# 5_wled.net
KiCad netlist of a schematic drawn in Altium Designer
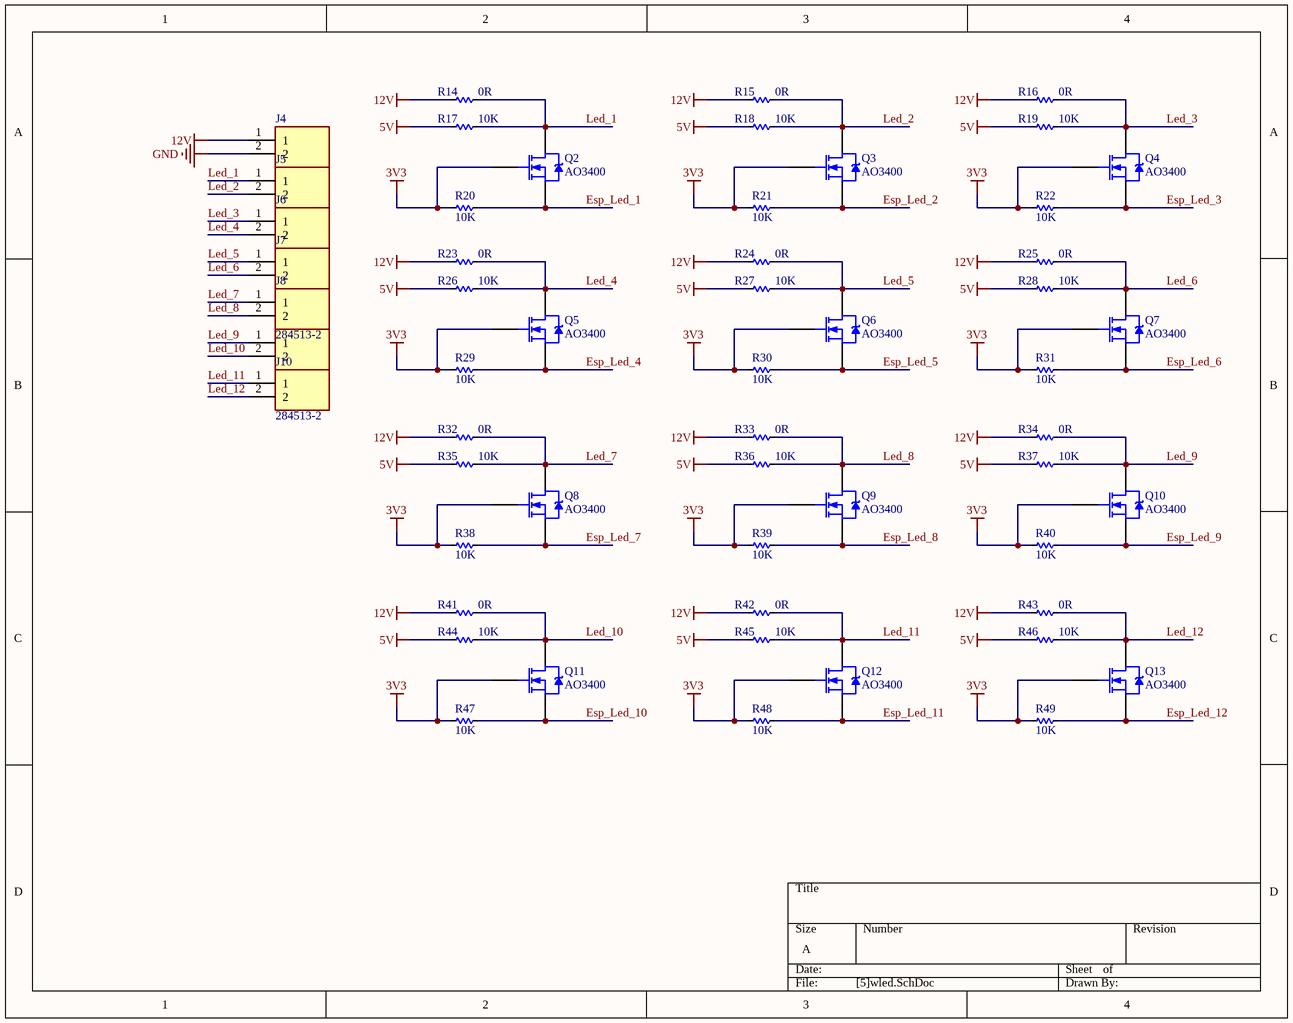
[diagram p0: [5]wled.SchDoc]

(export (version "E")
  (design (tool "Eeschema 10.0.6"))
  (components
    (comp (ref "J4")
      (value "284513-2")
      (footprint "SamacSys:SHDRRA2W80P0X381_1X2_863X920X730P")
      (description "Connector")
      (fields (field (name "MOUSER PART NUMBER") "571-284513-2"))
      (libsource (lib "SamacSys") (part "284513-2"))
    )
    (comp (ref "J5")
      (value "284513-2")
      (footprint "SamacSys:SHDRRA2W80P0X381_1X2_863X920X730P")
      (description "Connector")
      (fields (field (name "MOUSER PART NUMBER") "571-284513-2"))
      (libsource (lib "SamacSys") (part "284513-2"))
    )
    (comp (ref "J6")
      (value "284513-2")
      (footprint "SamacSys:SHDRRA2W80P0X381_1X2_863X920X730P")
      (description "Connector")
      (fields (field (name "MOUSER PART NUMBER") "571-284513-2"))
      (libsource (lib "SamacSys") (part "284513-2"))
    )
    (comp (ref "J7")
      (value "284513-2")
      (footprint "SamacSys:SHDRRA2W80P0X381_1X2_863X920X730P")
      (description "Connector")
      (fields (field (name "MOUSER PART NUMBER") "571-284513-2"))
      (libsource (lib "SamacSys") (part "284513-2"))
    )
    (comp (ref "J8")
      (value "284513-2")
      (footprint "SamacSys:SHDRRA2W80P0X381_1X2_863X920X730P")
      (description "Connector")
      (fields (field (name "MOUSER PART NUMBER") "571-284513-2"))
      (libsource (lib "SamacSys") (part "284513-2"))
    )
    (comp (ref "J9")
      (value "284513-2")
      (footprint "SamacSys:SHDRRA2W80P0X381_1X2_863X920X730P")
      (description "Connector")
      (fields (field (name "MOUSER PART NUMBER") "571-284513-2"))
      (libsource (lib "SamacSys") (part "284513-2"))
    )
    (comp (ref "J10")
      (value "284513-2")
      (footprint "SamacSys:SHDRRA2W80P0X381_1X2_863X920X730P")
      (description "Connector")
      (fields (field (name "MOUSER PART NUMBER") "571-284513-2"))
      (libsource (lib "SamacSys") (part "284513-2"))
    )
    (comp (ref "Q2")
      (value "AO3400")
      (footprint "SOT-23_N")
      (description "HEXFET Power MOSFET")
      (fields (field (name "PUBLISHER") "Altium Limited"))
      (libsource (lib "IR Discrete MOSFET - Power") (part "IRLML2402"))
    )
    (comp (ref "Q3")
      (value "AO3400")
      (footprint "SOT-23_N")
      (description "HEXFET Power MOSFET")
      (fields (field (name "PUBLISHER") "Altium Limited"))
      (libsource (lib "IR Discrete MOSFET - Power") (part "IRLML2402"))
    )
    (comp (ref "Q4")
      (value "AO3400")
      (footprint "SOT-23_N")
      (description "HEXFET Power MOSFET")
      (fields (field (name "PUBLISHER") "Altium Limited"))
      (libsource (lib "IR Discrete MOSFET - Power") (part "IRLML2402"))
    )
    (comp (ref "Q5")
      (value "AO3400")
      (footprint "SOT-23_N")
      (description "HEXFET Power MOSFET")
      (fields (field (name "PUBLISHER") "Altium Limited"))
      (libsource (lib "IR Discrete MOSFET - Power") (part "IRLML2402"))
    )
    (comp (ref "Q6")
      (value "AO3400")
      (footprint "SOT-23_N")
      (description "HEXFET Power MOSFET")
      (fields (field (name "PUBLISHER") "Altium Limited"))
      (libsource (lib "IR Discrete MOSFET - Power") (part "IRLML2402"))
    )
    (comp (ref "Q7")
      (value "AO3400")
      (footprint "SOT-23_N")
      (description "HEXFET Power MOSFET")
      (fields (field (name "PUBLISHER") "Altium Limited"))
      (libsource (lib "IR Discrete MOSFET - Power") (part "IRLML2402"))
    )
    (comp (ref "Q8")
      (value "AO3400")
      (footprint "SOT-23_N")
      (description "HEXFET Power MOSFET")
      (fields (field (name "PUBLISHER") "Altium Limited"))
      (libsource (lib "IR Discrete MOSFET - Power") (part "IRLML2402"))
    )
    (comp (ref "Q9")
      (value "AO3400")
      (footprint "SOT-23_N")
      (description "HEXFET Power MOSFET")
      (fields (field (name "PUBLISHER") "Altium Limited"))
      (libsource (lib "IR Discrete MOSFET - Power") (part "IRLML2402"))
    )
    (comp (ref "Q10")
      (value "AO3400")
      (footprint "SOT-23_N")
      (description "HEXFET Power MOSFET")
      (fields (field (name "PUBLISHER") "Altium Limited"))
      (libsource (lib "IR Discrete MOSFET - Power") (part "IRLML2402"))
    )
    (comp (ref "Q11")
      (value "AO3400")
      (footprint "SOT-23_N")
      (description "HEXFET Power MOSFET")
      (fields (field (name "PUBLISHER") "Altium Limited"))
      (libsource (lib "IR Discrete MOSFET - Power") (part "IRLML2402"))
    )
    (comp (ref "Q12")
      (value "AO3400")
      (footprint "SOT-23_N")
      (description "HEXFET Power MOSFET")
      (fields (field (name "PUBLISHER") "Altium Limited"))
      (libsource (lib "IR Discrete MOSFET - Power") (part "IRLML2402"))
    )
    (comp (ref "Q13")
      (value "AO3400")
      (footprint "SOT-23_N")
      (description "HEXFET Power MOSFET")
      (fields (field (name "PUBLISHER") "Altium Limited"))
      (libsource (lib "IR Discrete MOSFET - Power") (part "IRLML2402"))
    )
    (comp (ref "R14")
      (value "0R")
      (footprint "RES-SMD-0805")
      (description "Resistor")
      (fields
        (field (name "MANUFACTURER") "Generic Components")
        (field (name "PUBLISHER") "Altium Hobart Technology Centre")
      )
      (libsource (lib "LIBRARY") (part "Res-SMD"))
    )
    (comp (ref "R15")
      (value "0R")
      (footprint "RES-SMD-0805")
      (description "Resistor")
      (fields
        (field (name "MANUFACTURER") "Generic Components")
        (field (name "PUBLISHER") "Altium Hobart Technology Centre")
      )
      (libsource (lib "LIBRARY") (part "Res-SMD"))
    )
    (comp (ref "R16")
      (value "0R")
      (footprint "RES-SMD-0805")
      (description "Resistor")
      (fields
        (field (name "MANUFACTURER") "Generic Components")
        (field (name "PUBLISHER") "Altium Hobart Technology Centre")
      )
      (libsource (lib "LIBRARY") (part "Res-SMD"))
    )
    (comp (ref "R17")
      (value "10K")
      (footprint "RES-SMD-0805")
      (description "Resistor")
      (fields
        (field (name "MANUFACTURER") "Generic Components")
        (field (name "PUBLISHER") "Altium Hobart Technology Centre")
      )
      (libsource (lib "LIBRARY") (part "Res-SMD"))
    )
    (comp (ref "R18")
      (value "10K")
      (footprint "RES-SMD-0805")
      (description "Resistor")
      (fields
        (field (name "MANUFACTURER") "Generic Components")
        (field (name "PUBLISHER") "Altium Hobart Technology Centre")
      )
      (libsource (lib "LIBRARY") (part "Res-SMD"))
    )
    (comp (ref "R19")
      (value "10K")
      (footprint "RES-SMD-0805")
      (description "Resistor")
      (fields
        (field (name "MANUFACTURER") "Generic Components")
        (field (name "PUBLISHER") "Altium Hobart Technology Centre")
      )
      (libsource (lib "LIBRARY") (part "Res-SMD"))
    )
    (comp (ref "R20")
      (value "10K")
      (footprint "RES-SMD-0805")
      (description "Resistor")
      (fields
        (field (name "MANUFACTURER") "Generic Components")
        (field (name "PUBLISHER") "Altium Hobart Technology Centre")
      )
      (libsource (lib "LIBRARY") (part "Res-SMD"))
    )
    (comp (ref "R21")
      (value "10K")
      (footprint "RES-SMD-0805")
      (description "Resistor")
      (fields
        (field (name "MANUFACTURER") "Generic Components")
        (field (name "PUBLISHER") "Altium Hobart Technology Centre")
      )
      (libsource (lib "LIBRARY") (part "Res-SMD"))
    )
    (comp (ref "R22")
      (value "10K")
      (footprint "RES-SMD-0805")
      (description "Resistor")
      (fields
        (field (name "MANUFACTURER") "Generic Components")
        (field (name "PUBLISHER") "Altium Hobart Technology Centre")
      )
      (libsource (lib "LIBRARY") (part "Res-SMD"))
    )
    (comp (ref "R23")
      (value "0R")
      (footprint "RES-SMD-0805")
      (description "Resistor")
      (fields
        (field (name "MANUFACTURER") "Generic Components")
        (field (name "PUBLISHER") "Altium Hobart Technology Centre")
      )
      (libsource (lib "LIBRARY") (part "Res-SMD"))
    )
    (comp (ref "R24")
      (value "0R")
      (footprint "RES-SMD-0805")
      (description "Resistor")
      (fields
        (field (name "MANUFACTURER") "Generic Components")
        (field (name "PUBLISHER") "Altium Hobart Technology Centre")
      )
      (libsource (lib "LIBRARY") (part "Res-SMD"))
    )
    (comp (ref "R25")
      (value "0R")
      (footprint "RES-SMD-0805")
      (description "Resistor")
      (fields
        (field (name "MANUFACTURER") "Generic Components")
        (field (name "PUBLISHER") "Altium Hobart Technology Centre")
      )
      (libsource (lib "LIBRARY") (part "Res-SMD"))
    )
    (comp (ref "R26")
      (value "10K")
      (footprint "RES-SMD-0805")
      (description "Resistor")
      (fields
        (field (name "MANUFACTURER") "Generic Components")
        (field (name "PUBLISHER") "Altium Hobart Technology Centre")
      )
      (libsource (lib "LIBRARY") (part "Res-SMD"))
    )
    (comp (ref "R27")
      (value "10K")
      (footprint "RES-SMD-0805")
      (description "Resistor")
      (fields
        (field (name "MANUFACTURER") "Generic Components")
        (field (name "PUBLISHER") "Altium Hobart Technology Centre")
      )
      (libsource (lib "LIBRARY") (part "Res-SMD"))
    )
    (comp (ref "R28")
      (value "10K")
      (footprint "RES-SMD-0805")
      (description "Resistor")
      (fields
        (field (name "MANUFACTURER") "Generic Components")
        (field (name "PUBLISHER") "Altium Hobart Technology Centre")
      )
      (libsource (lib "LIBRARY") (part "Res-SMD"))
    )
    (comp (ref "R29")
      (value "10K")
      (footprint "RES-SMD-0805")
      (description "Resistor")
      (fields
        (field (name "MANUFACTURER") "Generic Components")
        (field (name "PUBLISHER") "Altium Hobart Technology Centre")
      )
      (libsource (lib "LIBRARY") (part "Res-SMD"))
    )
    (comp (ref "R30")
      (value "10K")
      (footprint "RES-SMD-0805")
      (description "Resistor")
      (fields
        (field (name "MANUFACTURER") "Generic Components")
        (field (name "PUBLISHER") "Altium Hobart Technology Centre")
      )
      (libsource (lib "LIBRARY") (part "Res-SMD"))
    )
    (comp (ref "R31")
      (value "10K")
      (footprint "RES-SMD-0805")
      (description "Resistor")
      (fields
        (field (name "MANUFACTURER") "Generic Components")
        (field (name "PUBLISHER") "Altium Hobart Technology Centre")
      )
      (libsource (lib "LIBRARY") (part "Res-SMD"))
    )
    (comp (ref "R32")
      (value "0R")
      (footprint "RES-SMD-0805")
      (description "Resistor")
      (fields
        (field (name "MANUFACTURER") "Generic Components")
        (field (name "PUBLISHER") "Altium Hobart Technology Centre")
      )
      (libsource (lib "LIBRARY") (part "Res-SMD"))
    )
    (comp (ref "R33")
      (value "0R")
      (footprint "RES-SMD-0805")
      (description "Resistor")
      (fields
        (field (name "MANUFACTURER") "Generic Components")
        (field (name "PUBLISHER") "Altium Hobart Technology Centre")
      )
      (libsource (lib "LIBRARY") (part "Res-SMD"))
    )
    (comp (ref "R34")
      (value "0R")
      (footprint "RES-SMD-0805")
      (description "Resistor")
      (fields
        (field (name "MANUFACTURER") "Generic Components")
        (field (name "PUBLISHER") "Altium Hobart Technology Centre")
      )
      (libsource (lib "LIBRARY") (part "Res-SMD"))
    )
    (comp (ref "R35")
      (value "10K")
      (footprint "RES-SMD-0805")
      (description "Resistor")
      (fields
        (field (name "MANUFACTURER") "Generic Components")
        (field (name "PUBLISHER") "Altium Hobart Technology Centre")
      )
      (libsource (lib "LIBRARY") (part "Res-SMD"))
    )
    (comp (ref "R36")
      (value "10K")
      (footprint "RES-SMD-0805")
      (description "Resistor")
      (fields
        (field (name "MANUFACTURER") "Generic Components")
        (field (name "PUBLISHER") "Altium Hobart Technology Centre")
      )
      (libsource (lib "LIBRARY") (part "Res-SMD"))
    )
    (comp (ref "R37")
      (value "10K")
      (footprint "RES-SMD-0805")
      (description "Resistor")
      (fields
        (field (name "MANUFACTURER") "Generic Components")
        (field (name "PUBLISHER") "Altium Hobart Technology Centre")
      )
      (libsource (lib "LIBRARY") (part "Res-SMD"))
    )
    (comp (ref "R38")
      (value "10K")
      (footprint "RES-SMD-0805")
      (description "Resistor")
      (fields
        (field (name "MANUFACTURER") "Generic Components")
        (field (name "PUBLISHER") "Altium Hobart Technology Centre")
      )
      (libsource (lib "LIBRARY") (part "Res-SMD"))
    )
    (comp (ref "R39")
      (value "10K")
      (footprint "RES-SMD-0805")
      (description "Resistor")
      (fields
        (field (name "MANUFACTURER") "Generic Components")
        (field (name "PUBLISHER") "Altium Hobart Technology Centre")
      )
      (libsource (lib "LIBRARY") (part "Res-SMD"))
    )
    (comp (ref "R40")
      (value "10K")
      (footprint "RES-SMD-0805")
      (description "Resistor")
      (fields
        (field (name "MANUFACTURER") "Generic Components")
        (field (name "PUBLISHER") "Altium Hobart Technology Centre")
      )
      (libsource (lib "LIBRARY") (part "Res-SMD"))
    )
    (comp (ref "R41")
      (value "0R")
      (footprint "RES-SMD-0805")
      (description "Resistor")
      (fields
        (field (name "MANUFACTURER") "Generic Components")
        (field (name "PUBLISHER") "Altium Hobart Technology Centre")
      )
      (libsource (lib "LIBRARY") (part "Res-SMD"))
    )
    (comp (ref "R42")
      (value "0R")
      (footprint "RES-SMD-0805")
      (description "Resistor")
      (fields
        (field (name "MANUFACTURER") "Generic Components")
        (field (name "PUBLISHER") "Altium Hobart Technology Centre")
      )
      (libsource (lib "LIBRARY") (part "Res-SMD"))
    )
    (comp (ref "R43")
      (value "0R")
      (footprint "RES-SMD-0805")
      (description "Resistor")
      (fields
        (field (name "MANUFACTURER") "Generic Components")
        (field (name "PUBLISHER") "Altium Hobart Technology Centre")
      )
      (libsource (lib "LIBRARY") (part "Res-SMD"))
    )
    (comp (ref "R44")
      (value "10K")
      (footprint "RES-SMD-0805")
      (description "Resistor")
      (fields
        (field (name "MANUFACTURER") "Generic Components")
        (field (name "PUBLISHER") "Altium Hobart Technology Centre")
      )
      (libsource (lib "LIBRARY") (part "Res-SMD"))
    )
    (comp (ref "R45")
      (value "10K")
      (footprint "RES-SMD-0805")
      (description "Resistor")
      (fields
        (field (name "MANUFACTURER") "Generic Components")
        (field (name "PUBLISHER") "Altium Hobart Technology Centre")
      )
      (libsource (lib "LIBRARY") (part "Res-SMD"))
    )
    (comp (ref "R46")
      (value "10K")
      (footprint "RES-SMD-0805")
      (description "Resistor")
      (fields
        (field (name "MANUFACTURER") "Generic Components")
        (field (name "PUBLISHER") "Altium Hobart Technology Centre")
      )
      (libsource (lib "LIBRARY") (part "Res-SMD"))
    )
    (comp (ref "R47")
      (value "10K")
      (footprint "RES-SMD-0805")
      (description "Resistor")
      (fields
        (field (name "MANUFACTURER") "Generic Components")
        (field (name "PUBLISHER") "Altium Hobart Technology Centre")
      )
      (libsource (lib "LIBRARY") (part "Res-SMD"))
    )
    (comp (ref "R48")
      (value "10K")
      (footprint "RES-SMD-0805")
      (description "Resistor")
      (fields
        (field (name "MANUFACTURER") "Generic Components")
        (field (name "PUBLISHER") "Altium Hobart Technology Centre")
      )
      (libsource (lib "LIBRARY") (part "Res-SMD"))
    )
    (comp (ref "R49")
      (value "10K")
      (footprint "RES-SMD-0805")
      (description "Resistor")
      (fields
        (field (name "MANUFACTURER") "Generic Components")
        (field (name "PUBLISHER") "Altium Hobart Technology Centre")
      )
      (libsource (lib "LIBRARY") (part "Res-SMD"))
    )
  )
  (nets
    (net (code "1") (name "/Esp_Led_1") (class "Default")
      (node (ref "Q2") (pin "2") (pinfunction "S_2") (pintype "passive"))
      (node (ref "R20") (pin "2") (pinfunction "2_2") (pintype "passive"))
    )
    (net (code "2") (name "/Esp_Led_2") (class "Default")
      (node (ref "Q3") (pin "2") (pinfunction "S_2") (pintype "passive"))
      (node (ref "R21") (pin "2") (pinfunction "2_2") (pintype "passive"))
    )
    (net (code "3") (name "/Esp_Led_3") (class "Default")
      (node (ref "Q4") (pin "2") (pinfunction "S_2") (pintype "passive"))
      (node (ref "R22") (pin "2") (pinfunction "2_2") (pintype "passive"))
    )
    (net (code "4") (name "/Esp_Led_4") (class "Default")
      (node (ref "Q5") (pin "2") (pinfunction "S_2") (pintype "passive"))
      (node (ref "R29") (pin "2") (pinfunction "2_2") (pintype "passive"))
    )
    (net (code "5") (name "/Esp_Led_5") (class "Default")
      (node (ref "Q6") (pin "2") (pinfunction "S_2") (pintype "passive"))
      (node (ref "R30") (pin "2") (pinfunction "2_2") (pintype "passive"))
    )
    (net (code "6") (name "/Esp_Led_6") (class "Default")
      (node (ref "Q7") (pin "2") (pinfunction "S_2") (pintype "passive"))
      (node (ref "R31") (pin "2") (pinfunction "2_2") (pintype "passive"))
    )
    (net (code "7") (name "/Esp_Led_7") (class "Default")
      (node (ref "Q8") (pin "2") (pinfunction "S_2") (pintype "passive"))
      (node (ref "R38") (pin "2") (pinfunction "2_2") (pintype "passive"))
    )
    (net (code "8") (name "/Esp_Led_8") (class "Default")
      (node (ref "Q9") (pin "2") (pinfunction "S_2") (pintype "passive"))
      (node (ref "R39") (pin "2") (pinfunction "2_2") (pintype "passive"))
    )
    (net (code "9") (name "/Esp_Led_9") (class "Default")
      (node (ref "Q10") (pin "2") (pinfunction "S_2") (pintype "passive"))
      (node (ref "R40") (pin "2") (pinfunction "2_2") (pintype "passive"))
    )
    (net (code "10") (name "/Esp_Led_10") (class "Default")
      (node (ref "Q11") (pin "2") (pinfunction "S_2") (pintype "passive"))
      (node (ref "R47") (pin "2") (pinfunction "2_2") (pintype "passive"))
    )
    (net (code "11") (name "/Esp_Led_11") (class "Default")
      (node (ref "Q12") (pin "2") (pinfunction "S_2") (pintype "passive"))
      (node (ref "R48") (pin "2") (pinfunction "2_2") (pintype "passive"))
    )
    (net (code "12") (name "/Esp_Led_12") (class "Default")
      (node (ref "Q13") (pin "2") (pinfunction "S_2") (pintype "passive"))
      (node (ref "R49") (pin "2") (pinfunction "2_2") (pintype "passive"))
    )
    (net (code "13") (name "/Led_1") (class "Default")
      (node (ref "J5") (pin "1") (pinfunction "1_1") (pintype "passive"))
      (node (ref "Q2") (pin "3") (pinfunction "D_3") (pintype "passive"))
      (node (ref "R14") (pin "2") (pinfunction "2_2") (pintype "passive"))
      (node (ref "R17") (pin "2") (pinfunction "2_2") (pintype "passive"))
    )
    (net (code "14") (name "/Led_2") (class "Default")
      (node (ref "J5") (pin "2") (pinfunction "2_2") (pintype "passive"))
      (node (ref "Q3") (pin "3") (pinfunction "D_3") (pintype "passive"))
      (node (ref "R15") (pin "2") (pinfunction "2_2") (pintype "passive"))
      (node (ref "R18") (pin "2") (pinfunction "2_2") (pintype "passive"))
    )
    (net (code "15") (name "/Led_3") (class "Default")
      (node (ref "J6") (pin "1") (pinfunction "1_1") (pintype "passive"))
      (node (ref "Q4") (pin "3") (pinfunction "D_3") (pintype "passive"))
      (node (ref "R16") (pin "2") (pinfunction "2_2") (pintype "passive"))
      (node (ref "R19") (pin "2") (pinfunction "2_2") (pintype "passive"))
    )
    (net (code "16") (name "/Led_4") (class "Default")
      (node (ref "J6") (pin "2") (pinfunction "2_2") (pintype "passive"))
      (node (ref "Q5") (pin "3") (pinfunction "D_3") (pintype "passive"))
      (node (ref "R23") (pin "2") (pinfunction "2_2") (pintype "passive"))
      (node (ref "R26") (pin "2") (pinfunction "2_2") (pintype "passive"))
    )
    (net (code "17") (name "/Led_5") (class "Default")
      (node (ref "J7") (pin "1") (pinfunction "1_1") (pintype "passive"))
      (node (ref "Q6") (pin "3") (pinfunction "D_3") (pintype "passive"))
      (node (ref "R24") (pin "2") (pinfunction "2_2") (pintype "passive"))
      (node (ref "R27") (pin "2") (pinfunction "2_2") (pintype "passive"))
    )
    (net (code "18") (name "/Led_6") (class "Default")
      (node (ref "J7") (pin "2") (pinfunction "2_2") (pintype "passive"))
      (node (ref "Q7") (pin "3") (pinfunction "D_3") (pintype "passive"))
      (node (ref "R25") (pin "2") (pinfunction "2_2") (pintype "passive"))
      (node (ref "R28") (pin "2") (pinfunction "2_2") (pintype "passive"))
    )
    (net (code "19") (name "/Led_7") (class "Default")
      (node (ref "J8") (pin "1") (pinfunction "1_1") (pintype "passive"))
      (node (ref "Q8") (pin "3") (pinfunction "D_3") (pintype "passive"))
      (node (ref "R32") (pin "2") (pinfunction "2_2") (pintype "passive"))
      (node (ref "R35") (pin "2") (pinfunction "2_2") (pintype "passive"))
    )
    (net (code "20") (name "/Led_8") (class "Default")
      (node (ref "J8") (pin "2") (pinfunction "2_2") (pintype "passive"))
      (node (ref "Q9") (pin "3") (pinfunction "D_3") (pintype "passive"))
      (node (ref "R33") (pin "2") (pinfunction "2_2") (pintype "passive"))
      (node (ref "R36") (pin "2") (pinfunction "2_2") (pintype "passive"))
    )
    (net (code "21") (name "/Led_9") (class "Default")
      (node (ref "J9") (pin "1") (pinfunction "1_1") (pintype "passive"))
      (node (ref "Q10") (pin "3") (pinfunction "D_3") (pintype "passive"))
      (node (ref "R34") (pin "2") (pinfunction "2_2") (pintype "passive"))
      (node (ref "R37") (pin "2") (pinfunction "2_2") (pintype "passive"))
    )
    (net (code "22") (name "/Led_10") (class "Default")
      (node (ref "J9") (pin "2") (pinfunction "2_2") (pintype "passive"))
      (node (ref "Q11") (pin "3") (pinfunction "D_3") (pintype "passive"))
      (node (ref "R41") (pin "2") (pinfunction "2_2") (pintype "passive"))
      (node (ref "R44") (pin "2") (pinfunction "2_2") (pintype "passive"))
    )
    (net (code "23") (name "/Led_11") (class "Default")
      (node (ref "J10") (pin "1") (pinfunction "1_1") (pintype "passive"))
      (node (ref "Q12") (pin "3") (pinfunction "D_3") (pintype "passive"))
      (node (ref "R42") (pin "2") (pinfunction "2_2") (pintype "passive"))
      (node (ref "R45") (pin "2") (pinfunction "2_2") (pintype "passive"))
    )
    (net (code "24") (name "/Led_12") (class "Default")
      (node (ref "J10") (pin "2") (pinfunction "2_2") (pintype "passive"))
      (node (ref "Q13") (pin "3") (pinfunction "D_3") (pintype "passive"))
      (node (ref "R43") (pin "2") (pinfunction "2_2") (pintype "passive"))
      (node (ref "R46") (pin "2") (pinfunction "2_2") (pintype "passive"))
    )
    (net (code "25") (name "3V3") (class "Default")
      (node (ref "Q10") (pin "1") (pinfunction "G_1") (pintype "passive"))
      (node (ref "Q11") (pin "1") (pinfunction "G_1") (pintype "passive"))
      (node (ref "Q12") (pin "1") (pinfunction "G_1") (pintype "passive"))
      (node (ref "Q13") (pin "1") (pinfunction "G_1") (pintype "passive"))
      (node (ref "Q2") (pin "1") (pinfunction "G_1") (pintype "passive"))
      (node (ref "Q3") (pin "1") (pinfunction "G_1") (pintype "passive"))
      (node (ref "Q4") (pin "1") (pinfunction "G_1") (pintype "passive"))
      (node (ref "Q5") (pin "1") (pinfunction "G_1") (pintype "passive"))
      (node (ref "Q6") (pin "1") (pinfunction "G_1") (pintype "passive"))
      (node (ref "Q7") (pin "1") (pinfunction "G_1") (pintype "passive"))
      (node (ref "Q8") (pin "1") (pinfunction "G_1") (pintype "passive"))
      (node (ref "Q9") (pin "1") (pinfunction "G_1") (pintype "passive"))
      (node (ref "R20") (pin "1") (pinfunction "1_1") (pintype "passive"))
      (node (ref "R21") (pin "1") (pinfunction "1_1") (pintype "passive"))
      (node (ref "R22") (pin "1") (pinfunction "1_1") (pintype "passive"))
      (node (ref "R29") (pin "1") (pinfunction "1_1") (pintype "passive"))
      (node (ref "R30") (pin "1") (pinfunction "1_1") (pintype "passive"))
      (node (ref "R31") (pin "1") (pinfunction "1_1") (pintype "passive"))
      (node (ref "R38") (pin "1") (pinfunction "1_1") (pintype "passive"))
      (node (ref "R39") (pin "1") (pinfunction "1_1") (pintype "passive"))
      (node (ref "R40") (pin "1") (pinfunction "1_1") (pintype "passive"))
      (node (ref "R47") (pin "1") (pinfunction "1_1") (pintype "passive"))
      (node (ref "R48") (pin "1") (pinfunction "1_1") (pintype "passive"))
      (node (ref "R49") (pin "1") (pinfunction "1_1") (pintype "passive"))
    )
    (net (code "26") (name "5V") (class "Default")
      (node (ref "R17") (pin "1") (pinfunction "1_1") (pintype "passive"))
      (node (ref "R18") (pin "1") (pinfunction "1_1") (pintype "passive"))
      (node (ref "R19") (pin "1") (pinfunction "1_1") (pintype "passive"))
      (node (ref "R26") (pin "1") (pinfunction "1_1") (pintype "passive"))
      (node (ref "R27") (pin "1") (pinfunction "1_1") (pintype "passive"))
      (node (ref "R28") (pin "1") (pinfunction "1_1") (pintype "passive"))
      (node (ref "R35") (pin "1") (pinfunction "1_1") (pintype "passive"))
      (node (ref "R36") (pin "1") (pinfunction "1_1") (pintype "passive"))
      (node (ref "R37") (pin "1") (pinfunction "1_1") (pintype "passive"))
      (node (ref "R44") (pin "1") (pinfunction "1_1") (pintype "passive"))
      (node (ref "R45") (pin "1") (pinfunction "1_1") (pintype "passive"))
      (node (ref "R46") (pin "1") (pinfunction "1_1") (pintype "passive"))
    )
    (net (code "27") (name "12V") (class "Default")
      (node (ref "J4") (pin "1") (pinfunction "1_1") (pintype "passive"))
      (node (ref "R14") (pin "1") (pinfunction "1_1") (pintype "passive"))
      (node (ref "R15") (pin "1") (pinfunction "1_1") (pintype "passive"))
      (node (ref "R16") (pin "1") (pinfunction "1_1") (pintype "passive"))
      (node (ref "R23") (pin "1") (pinfunction "1_1") (pintype "passive"))
      (node (ref "R24") (pin "1") (pinfunction "1_1") (pintype "passive"))
      (node (ref "R25") (pin "1") (pinfunction "1_1") (pintype "passive"))
      (node (ref "R32") (pin "1") (pinfunction "1_1") (pintype "passive"))
      (node (ref "R33") (pin "1") (pinfunction "1_1") (pintype "passive"))
      (node (ref "R34") (pin "1") (pinfunction "1_1") (pintype "passive"))
      (node (ref "R41") (pin "1") (pinfunction "1_1") (pintype "passive"))
      (node (ref "R42") (pin "1") (pinfunction "1_1") (pintype "passive"))
      (node (ref "R43") (pin "1") (pinfunction "1_1") (pintype "passive"))
    )
    (net (code "28") (name "GND") (class "Default")
      (node (ref "J4") (pin "2") (pinfunction "2_2") (pintype "passive"))
    )
  )
)
